# networking-node.net
KiCad netlist of a schematic drawn in EAGLE
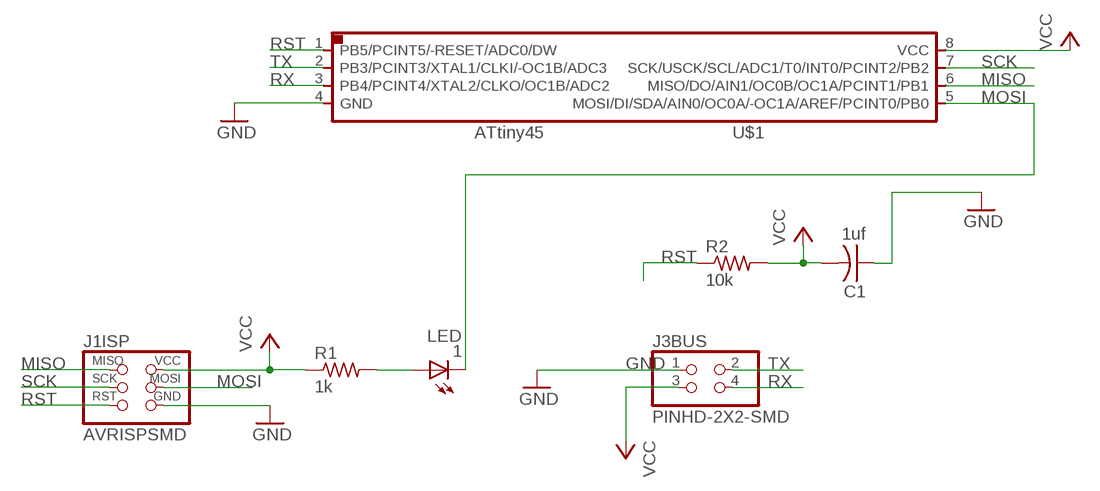
[diagram p0: schematic, sheet 1]

(export (version "E")
  (design (tool "Eeschema 10.0.6"))
  (components
    (comp (ref "1")
      (value "LED")
      (footprint "eagle-import:LED1206")
      (libsource (lib "eagle-import") (part "LED"))
    )
    (comp (ref "C1")
      (value "1uf")
      (footprint "eagle-import:C1206FAB")
      (libsource (lib "eagle-import") (part "CAP-US1206FAB"))
    )
    (comp (ref "J1ISP")
      (value "AVRISPSMD")
      (footprint "eagle-import:2X03SMD")
      (libsource (lib "eagle-import") (part "AVRISPSMD"))
    )
    (comp (ref "J3BUS")
      (value "PINHD-2X2-SMD")
      (footprint "eagle-import:2X02SMD")
      (libsource (lib "eagle-import") (part "PINHD-2X2-SMD"))
    )
    (comp (ref "R1")
      (value "1k")
      (footprint "eagle-import:R1206")
      (libsource (lib "eagle-import") (part "RES-US1206"))
    )
    (comp (ref "R2")
      (value "10k")
      (footprint "eagle-import:R1206")
      (libsource (lib "eagle-import") (part "RES-US1206"))
    )
    (comp (ref "U$1")
      (value "ATTINY45SI")
      (footprint "eagle-import:SOIC8")
      (libsource (lib "eagle-import") (part "ATTINY45SI"))
    )
  )
  (nets
    (net (code "1") (name "/MISO") (class "Default")
      (node (ref "J1ISP") (pin "1") (pinfunction "MISO_1") (pintype "passive"))
      (node (ref "U$1") (pin "6") (pinfunction "MISO/DO/AIN1/OC0B/OC1A/PCINT1/PB1_6") (pintype "bidirectional"))
    )
    (net (code "2") (name "/MOSI") (class "Default")
      (node (ref "1") (pin "2") (pinfunction "C_2") (pintype "passive"))
      (node (ref "J1ISP") (pin "4") (pinfunction "MOSI_4") (pintype "passive"))
      (node (ref "U$1") (pin "5") (pinfunction "MOSI/DI/SDA/AIN0/OC0A/-OC1A/AREF/PCINT0/PB0_5") (pintype "bidirectional"))
    )
    (net (code "3") (name "/RST") (class "Default")
      (node (ref "J1ISP") (pin "5") (pinfunction "RST_5") (pintype "passive"))
      (node (ref "R2") (pin "1") (pinfunction "1_1") (pintype "passive"))
      (node (ref "U$1") (pin "1") (pinfunction "PB5/PCINT5/-RESET/ADC0/DW_1") (pintype "bidirectional"))
    )
    (net (code "4") (name "/RX") (class "Default")
      (node (ref "J3BUS") (pin "4") (pinfunction "4_4") (pintype "passive"))
      (node (ref "U$1") (pin "3") (pinfunction "PB4/PCINT4/XTAL2/CLKO/OC1B/ADC2_3") (pintype "bidirectional"))
    )
    (net (code "5") (name "/SCK") (class "Default")
      (node (ref "J1ISP") (pin "3") (pinfunction "SCK_3") (pintype "passive"))
      (node (ref "U$1") (pin "7") (pinfunction "SCK/USCK/SCL/ADC1/T0/INT0/PCINT2/PB2_7") (pintype "bidirectional"))
    )
    (net (code "6") (name "/TX") (class "Default")
      (node (ref "J3BUS") (pin "2") (pinfunction "2_2") (pintype "passive"))
      (node (ref "U$1") (pin "2") (pinfunction "PB3/PCINT3/XTAL1/CLKI/-OC1B/ADC3_2") (pintype "bidirectional"))
    )
    (net (code "7") (name "GND") (class "Default")
      (node (ref "C1") (pin "1") (pinfunction "1_1") (pintype "passive"))
      (node (ref "J1ISP") (pin "6") (pinfunction "GND_6") (pintype "passive"))
      (node (ref "J3BUS") (pin "1") (pinfunction "1_1") (pintype "passive"))
      (node (ref "U$1") (pin "4") (pinfunction "GND_4") (pintype "bidirectional"))
    )
    (net (code "8") (name "Net-(1-A)") (class "Default")
      (node (ref "1") (pin "1") (pinfunction "A_1") (pintype "passive"))
      (node (ref "R1") (pin "2") (pinfunction "2_2") (pintype "passive"))
    )
    (net (code "9") (name "VCC") (class "Default")
      (node (ref "C1") (pin "2") (pinfunction "2_2") (pintype "passive"))
      (node (ref "J1ISP") (pin "2") (pinfunction "VCC_2") (pintype "passive"))
      (node (ref "J3BUS") (pin "3") (pinfunction "3_3") (pintype "passive"))
      (node (ref "R1") (pin "1") (pinfunction "1_1") (pintype "passive"))
      (node (ref "R2") (pin "2") (pinfunction "2_2") (pintype "passive"))
      (node (ref "U$1") (pin "8") (pinfunction "VCC_8") (pintype "bidirectional"))
    )
  )
)
